# SDRAM_16Mx32.net
KiCad netlist of a schematic drawn in Altium Designer
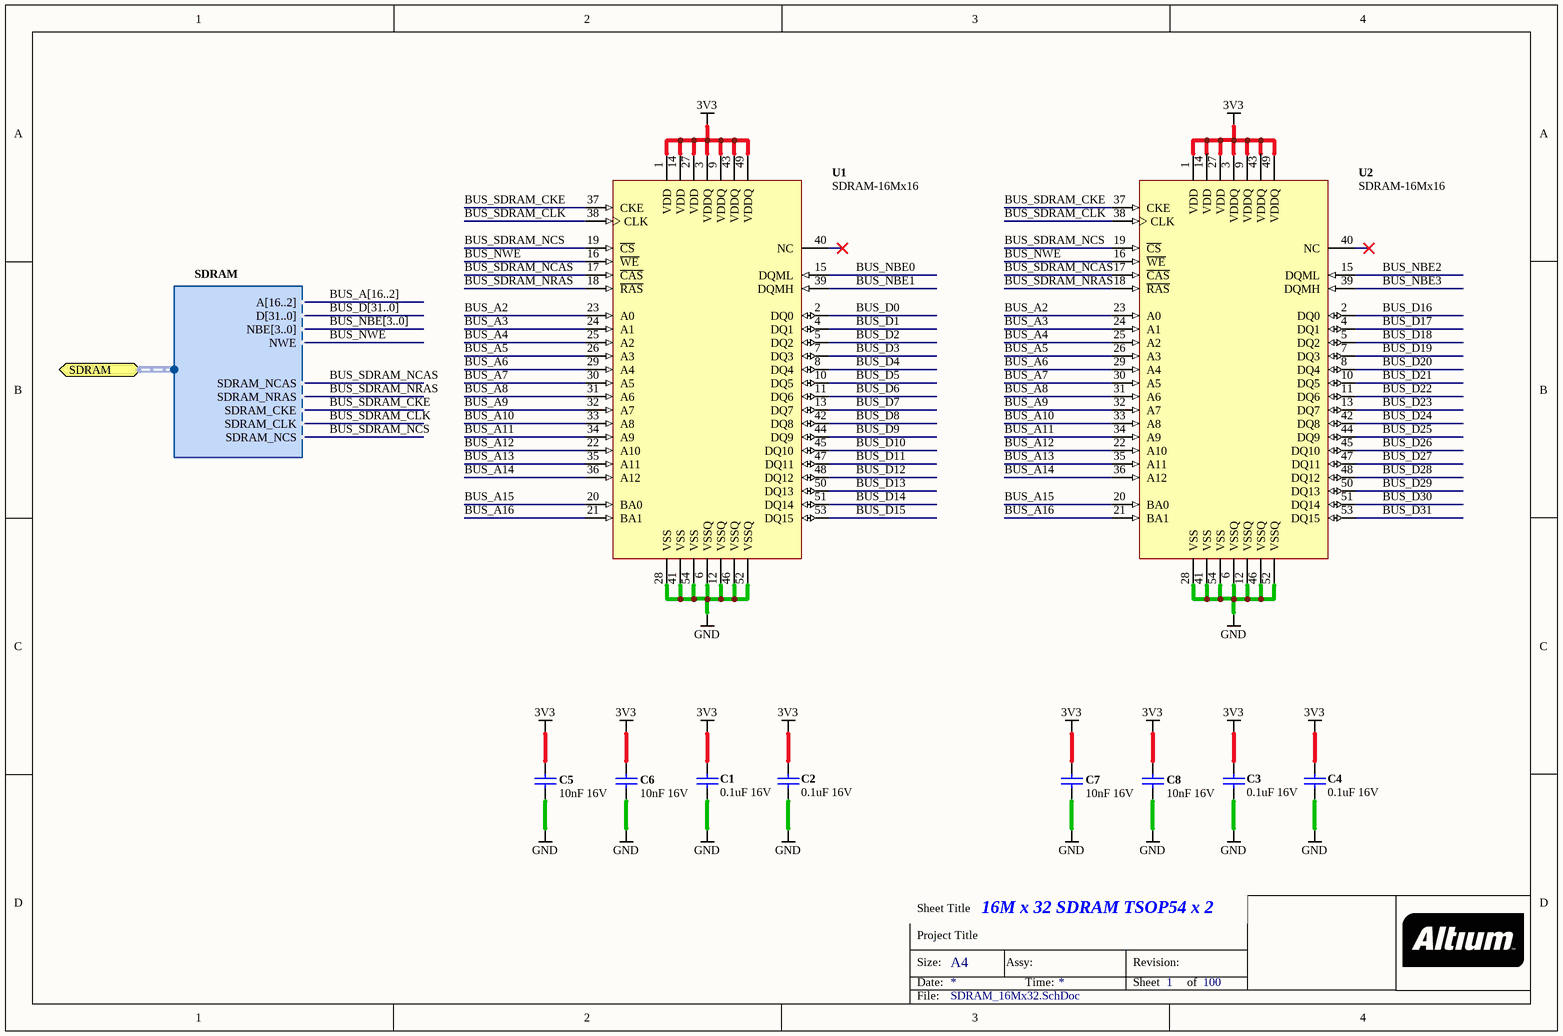
[diagram p0: SDRAM_16Mx32.SchDoc]

(export (version "E")
  (design (tool "Eeschema 10.0.6"))
  (components
    (comp (ref "C1")
      (value "0.1uF 16V")
      (footprint "CAPC1005-STAR")
      (description "Capacitor, Ceramic, 0.1uF 10% 16V 0402 (1005) X7R")
      (fields (field (name "TOLERANCE") "10 %"))
      (libsource (lib "altium-import") (part "root_0_mirrored_CAP-NP_"))
    )
    (comp (ref "C2")
      (value "0.1uF 16V")
      (footprint "CAPC1005-STAR")
      (description "Capacitor, Ceramic, 0.1uF 10% 16V 0402 (1005) X7R")
      (fields (field (name "TOLERANCE") "10 %"))
      (libsource (lib "altium-import") (part "root_0_mirrored_CAP-NP_"))
    )
    (comp (ref "C3")
      (value "0.1uF 16V")
      (footprint "CAPC1005-STAR")
      (description "Capacitor, Ceramic, 0.1uF 10% 16V 0402 (1005) X7R")
      (fields (field (name "TOLERANCE") "10 %"))
      (libsource (lib "altium-import") (part "root_0_mirrored_CAP-NP_"))
    )
    (comp (ref "C4")
      (value "0.1uF 16V")
      (footprint "CAPC1005-STAR")
      (description "Capacitor, Ceramic, 0.1uF 10% 16V 0402 (1005) X7R")
      (fields (field (name "TOLERANCE") "10 %"))
      (libsource (lib "altium-import") (part "root_0_mirrored_CAP-NP_"))
    )
    (comp (ref "C5")
      (value "10nF 16V")
      (footprint "CAPC1005-STAR")
      (description "Capacitor, Ceramic, 10nF 10% 16V 0402 (1005) X7R")
      (fields (field (name "TOLERANCE") "10 %"))
      (libsource (lib "altium-import") (part "root_0_CAP-NP_"))
    )
    (comp (ref "C6")
      (value "10nF 16V")
      (footprint "CAPC1005-STAR")
      (description "Capacitor, Ceramic, 10nF 10% 16V 0402 (1005) X7R")
      (fields (field (name "TOLERANCE") "10 %"))
      (libsource (lib "altium-import") (part "root_0_CAP-NP_"))
    )
    (comp (ref "C7")
      (value "10nF 16V")
      (footprint "CAPC1005-STAR")
      (description "Capacitor, Ceramic, 10nF 10% 16V 0402 (1005) X7R")
      (fields (field (name "TOLERANCE") "10 %"))
      (libsource (lib "altium-import") (part "root_0_CAP-NP_"))
    )
    (comp (ref "C8")
      (value "10nF 16V")
      (footprint "CAPC1005-STAR")
      (description "Capacitor, Ceramic, 10nF 10% 16V 0402 (1005) X7R")
      (fields (field (name "TOLERANCE") "10 %"))
      (libsource (lib "altium-import") (part "root_0_CAP-NP_"))
    )
    (comp (ref "U1")
      (value "SDRAM-16Mx16")
      (footprint "TSOP80P1176-54")
      (description "MT48LC16M16A2TG, 256 Mbit High-Speed CMOS SDRAM, 16Mb x 16Bit x 4 Banks, TSOP54")
      (libsource (lib "altium-import") (part "root_0_MT48LC16M16A2TG_"))
    )
    (comp (ref "U2")
      (value "SDRAM-16Mx16")
      (footprint "TSOP80P1176-54")
      (description "MT48LC16M16A2TG, 256 Mbit High-Speed CMOS SDRAM, 16Mb x 16Bit x 4 Banks, TSOP54")
      (libsource (lib "altium-import") (part "root_0_MT48LC16M16A2TG_"))
    )
  )
  (nets
    (net (code "2") (name "/BUS_A2") (class "Default")
      (node (ref "U1") (pin "23") (pinfunction "A0_23") (pintype "input"))
      (node (ref "U2") (pin "23") (pinfunction "A0_23") (pintype "input"))
    )
    (net (code "3") (name "/BUS_A3") (class "Default")
      (node (ref "U1") (pin "24") (pinfunction "A1_24") (pintype "input"))
      (node (ref "U2") (pin "24") (pinfunction "A1_24") (pintype "input"))
    )
    (net (code "4") (name "/BUS_A4") (class "Default")
      (node (ref "U1") (pin "25") (pinfunction "A2_25") (pintype "input"))
      (node (ref "U2") (pin "25") (pinfunction "A2_25") (pintype "input"))
    )
    (net (code "5") (name "/BUS_A5") (class "Default")
      (node (ref "U1") (pin "26") (pinfunction "A3_26") (pintype "input"))
      (node (ref "U2") (pin "26") (pinfunction "A3_26") (pintype "input"))
    )
    (net (code "6") (name "/BUS_A6") (class "Default")
      (node (ref "U1") (pin "29") (pinfunction "A4_29") (pintype "input"))
      (node (ref "U2") (pin "29") (pinfunction "A4_29") (pintype "input"))
    )
    (net (code "7") (name "/BUS_A7") (class "Default")
      (node (ref "U1") (pin "30") (pinfunction "A5_30") (pintype "input"))
      (node (ref "U2") (pin "30") (pinfunction "A5_30") (pintype "input"))
    )
    (net (code "8") (name "/BUS_A8") (class "Default")
      (node (ref "U1") (pin "31") (pinfunction "A6_31") (pintype "input"))
      (node (ref "U2") (pin "31") (pinfunction "A6_31") (pintype "input"))
    )
    (net (code "9") (name "/BUS_A9") (class "Default")
      (node (ref "U1") (pin "32") (pinfunction "A7_32") (pintype "input"))
      (node (ref "U2") (pin "32") (pinfunction "A7_32") (pintype "input"))
    )
    (net (code "10") (name "/BUS_A10") (class "Default")
      (node (ref "U1") (pin "33") (pinfunction "A8_33") (pintype "input"))
      (node (ref "U2") (pin "33") (pinfunction "A8_33") (pintype "input"))
    )
    (net (code "11") (name "/BUS_A11") (class "Default")
      (node (ref "U1") (pin "34") (pinfunction "A9_34") (pintype "input"))
      (node (ref "U2") (pin "34") (pinfunction "A9_34") (pintype "input"))
    )
    (net (code "12") (name "/BUS_A12") (class "Default")
      (node (ref "U1") (pin "22") (pinfunction "A10_22") (pintype "input"))
      (node (ref "U2") (pin "22") (pinfunction "A10_22") (pintype "input"))
    )
    (net (code "13") (name "/BUS_A13") (class "Default")
      (node (ref "U1") (pin "35") (pinfunction "A11_35") (pintype "input"))
      (node (ref "U2") (pin "35") (pinfunction "A11_35") (pintype "input"))
    )
    (net (code "14") (name "/BUS_A14") (class "Default")
      (node (ref "U1") (pin "36") (pinfunction "A12_36") (pintype "input"))
      (node (ref "U2") (pin "36") (pinfunction "A12_36") (pintype "input"))
    )
    (net (code "15") (name "/BUS_A15") (class "Default")
      (node (ref "U1") (pin "20") (pinfunction "BA0_20") (pintype "input"))
      (node (ref "U2") (pin "20") (pinfunction "BA0_20") (pintype "input"))
    )
    (net (code "16") (name "/BUS_A16") (class "Default")
      (node (ref "U1") (pin "21") (pinfunction "BA1_21") (pintype "input"))
      (node (ref "U2") (pin "21") (pinfunction "BA1_21") (pintype "input"))
    )
    (net (code "18") (name "/BUS_D0") (class "Default")
      (node (ref "U1") (pin "2") (pinfunction "DQ0_2") (pintype "bidirectional"))
    )
    (net (code "19") (name "/BUS_D1") (class "Default")
      (node (ref "U1") (pin "4") (pinfunction "DQ1_4") (pintype "bidirectional"))
    )
    (net (code "20") (name "/BUS_D2") (class "Default")
      (node (ref "U1") (pin "5") (pinfunction "DQ2_5") (pintype "bidirectional"))
    )
    (net (code "21") (name "/BUS_D3") (class "Default")
      (node (ref "U1") (pin "7") (pinfunction "DQ3_7") (pintype "bidirectional"))
    )
    (net (code "22") (name "/BUS_D4") (class "Default")
      (node (ref "U1") (pin "8") (pinfunction "DQ4_8") (pintype "bidirectional"))
    )
    (net (code "23") (name "/BUS_D5") (class "Default")
      (node (ref "U1") (pin "10") (pinfunction "DQ5_10") (pintype "bidirectional"))
    )
    (net (code "24") (name "/BUS_D6") (class "Default")
      (node (ref "U1") (pin "11") (pinfunction "DQ6_11") (pintype "bidirectional"))
    )
    (net (code "25") (name "/BUS_D7") (class "Default")
      (node (ref "U1") (pin "13") (pinfunction "DQ7_13") (pintype "bidirectional"))
    )
    (net (code "26") (name "/BUS_D8") (class "Default")
      (node (ref "U1") (pin "42") (pinfunction "DQ8_42") (pintype "bidirectional"))
    )
    (net (code "27") (name "/BUS_D9") (class "Default")
      (node (ref "U1") (pin "44") (pinfunction "DQ9_44") (pintype "bidirectional"))
    )
    (net (code "28") (name "/BUS_D10") (class "Default")
      (node (ref "U1") (pin "45") (pinfunction "DQ10_45") (pintype "bidirectional"))
    )
    (net (code "29") (name "/BUS_D11") (class "Default")
      (node (ref "U1") (pin "47") (pinfunction "DQ11_47") (pintype "bidirectional"))
    )
    (net (code "30") (name "/BUS_D12") (class "Default")
      (node (ref "U1") (pin "48") (pinfunction "DQ12_48") (pintype "bidirectional"))
    )
    (net (code "31") (name "/BUS_D13") (class "Default")
      (node (ref "U1") (pin "50") (pinfunction "DQ13_50") (pintype "bidirectional"))
    )
    (net (code "32") (name "/BUS_D14") (class "Default")
      (node (ref "U1") (pin "51") (pinfunction "DQ14_51") (pintype "bidirectional"))
    )
    (net (code "33") (name "/BUS_D15") (class "Default")
      (node (ref "U1") (pin "53") (pinfunction "DQ15_53") (pintype "bidirectional"))
    )
    (net (code "34") (name "/BUS_D16") (class "Default")
      (node (ref "U2") (pin "2") (pinfunction "DQ0_2") (pintype "bidirectional"))
    )
    (net (code "35") (name "/BUS_D17") (class "Default")
      (node (ref "U2") (pin "4") (pinfunction "DQ1_4") (pintype "bidirectional"))
    )
    (net (code "36") (name "/BUS_D18") (class "Default")
      (node (ref "U2") (pin "5") (pinfunction "DQ2_5") (pintype "bidirectional"))
    )
    (net (code "37") (name "/BUS_D19") (class "Default")
      (node (ref "U2") (pin "7") (pinfunction "DQ3_7") (pintype "bidirectional"))
    )
    (net (code "38") (name "/BUS_D20") (class "Default")
      (node (ref "U2") (pin "8") (pinfunction "DQ4_8") (pintype "bidirectional"))
    )
    (net (code "39") (name "/BUS_D21") (class "Default")
      (node (ref "U2") (pin "10") (pinfunction "DQ5_10") (pintype "bidirectional"))
    )
    (net (code "40") (name "/BUS_D22") (class "Default")
      (node (ref "U2") (pin "11") (pinfunction "DQ6_11") (pintype "bidirectional"))
    )
    (net (code "41") (name "/BUS_D23") (class "Default")
      (node (ref "U2") (pin "13") (pinfunction "DQ7_13") (pintype "bidirectional"))
    )
    (net (code "42") (name "/BUS_D24") (class "Default")
      (node (ref "U2") (pin "42") (pinfunction "DQ8_42") (pintype "bidirectional"))
    )
    (net (code "43") (name "/BUS_D25") (class "Default")
      (node (ref "U2") (pin "44") (pinfunction "DQ9_44") (pintype "bidirectional"))
    )
    (net (code "44") (name "/BUS_D26") (class "Default")
      (node (ref "U2") (pin "45") (pinfunction "DQ10_45") (pintype "bidirectional"))
    )
    (net (code "45") (name "/BUS_D27") (class "Default")
      (node (ref "U2") (pin "47") (pinfunction "DQ11_47") (pintype "bidirectional"))
    )
    (net (code "46") (name "/BUS_D28") (class "Default")
      (node (ref "U2") (pin "48") (pinfunction "DQ12_48") (pintype "bidirectional"))
    )
    (net (code "47") (name "/BUS_D29") (class "Default")
      (node (ref "U2") (pin "50") (pinfunction "DQ13_50") (pintype "bidirectional"))
    )
    (net (code "48") (name "/BUS_D30") (class "Default")
      (node (ref "U2") (pin "51") (pinfunction "DQ14_51") (pintype "bidirectional"))
    )
    (net (code "49") (name "/BUS_D31") (class "Default")
      (node (ref "U2") (pin "53") (pinfunction "DQ15_53") (pintype "bidirectional"))
    )
    (net (code "51") (name "/BUS_NBE0") (class "Default")
      (node (ref "U1") (pin "15") (pinfunction "DQML_15") (pintype "input"))
    )
    (net (code "52") (name "/BUS_NBE1") (class "Default")
      (node (ref "U1") (pin "39") (pinfunction "DQMH_39") (pintype "input"))
    )
    (net (code "53") (name "/BUS_NBE2") (class "Default")
      (node (ref "U2") (pin "15") (pinfunction "DQML_15") (pintype "input"))
    )
    (net (code "54") (name "/BUS_NBE3") (class "Default")
      (node (ref "U2") (pin "39") (pinfunction "DQMH_39") (pintype "input"))
    )
    (net (code "56") (name "/BUS_NWE") (class "Default")
      (node (ref "U1") (pin "16") (pinfunction "~{WE}_16") (pintype "input"))
      (node (ref "U2") (pin "16") (pinfunction "~{WE}_16") (pintype "input"))
    )
    (net (code "57") (name "/BUS_SDRAM_CKE") (class "Default")
      (node (ref "U1") (pin "37") (pinfunction "CKE_37") (pintype "input"))
      (node (ref "U2") (pin "37") (pinfunction "CKE_37") (pintype "input"))
    )
    (net (code "58") (name "/BUS_SDRAM_CLK") (class "Default")
      (node (ref "U1") (pin "38") (pinfunction "CLK_38") (pintype "input"))
      (node (ref "U2") (pin "38") (pinfunction "CLK_38") (pintype "input"))
    )
    (net (code "59") (name "/BUS_SDRAM_NCAS") (class "Default")
      (node (ref "U1") (pin "17") (pinfunction "~{CAS}_17") (pintype "input"))
      (node (ref "U2") (pin "17") (pinfunction "~{CAS}_17") (pintype "input"))
    )
    (net (code "60") (name "/BUS_SDRAM_NCS") (class "Default")
      (node (ref "U1") (pin "19") (pinfunction "~{CS}_19") (pintype "input"))
      (node (ref "U2") (pin "19") (pinfunction "~{CS}_19") (pintype "input"))
    )
    (net (code "61") (name "/BUS_SDRAM_NRAS") (class "Default")
      (node (ref "U1") (pin "18") (pinfunction "~{RAS}_18") (pintype "input"))
      (node (ref "U2") (pin "18") (pinfunction "~{RAS}_18") (pintype "input"))
    )
    (net (code "63") (name "3V3") (class "Default")
      (node (ref "C1") (pin "1") (pinfunction "1_1") (pintype "passive"))
      (node (ref "C2") (pin "1") (pinfunction "1_1") (pintype "passive"))
      (node (ref "C3") (pin "1") (pinfunction "1_1") (pintype "passive"))
      (node (ref "C4") (pin "1") (pinfunction "1_1") (pintype "passive"))
      (node (ref "C5") (pin "1") (pinfunction "1_1") (pintype "passive"))
      (node (ref "C6") (pin "1") (pinfunction "1_1") (pintype "passive"))
      (node (ref "C7") (pin "1") (pinfunction "1_1") (pintype "passive"))
      (node (ref "C8") (pin "1") (pinfunction "1_1") (pintype "passive"))
      (node (ref "U1") (pin "1") (pinfunction "VDD_1") (pintype "power_in"))
      (node (ref "U1") (pin "14") (pinfunction "VDD_14") (pintype "power_in"))
      (node (ref "U1") (pin "27") (pinfunction "VDD_27") (pintype "power_in"))
      (node (ref "U1") (pin "3") (pinfunction "VDDQ_3") (pintype "power_in"))
      (node (ref "U1") (pin "43") (pinfunction "VDDQ_43") (pintype "power_in"))
      (node (ref "U1") (pin "49") (pinfunction "VDDQ_49") (pintype "power_in"))
      (node (ref "U1") (pin "9") (pinfunction "VDDQ_9") (pintype "power_in"))
      (node (ref "U2") (pin "1") (pinfunction "VDD_1") (pintype "power_in"))
      (node (ref "U2") (pin "14") (pinfunction "VDD_14") (pintype "power_in"))
      (node (ref "U2") (pin "27") (pinfunction "VDD_27") (pintype "power_in"))
      (node (ref "U2") (pin "3") (pinfunction "VDDQ_3") (pintype "power_in"))
      (node (ref "U2") (pin "43") (pinfunction "VDDQ_43") (pintype "power_in"))
      (node (ref "U2") (pin "49") (pinfunction "VDDQ_49") (pintype "power_in"))
      (node (ref "U2") (pin "9") (pinfunction "VDDQ_9") (pintype "power_in"))
    )
    (net (code "64") (name "GND") (class "Default")
      (node (ref "C1") (pin "2") (pinfunction "2_2") (pintype "passive"))
      (node (ref "C2") (pin "2") (pinfunction "2_2") (pintype "passive"))
      (node (ref "C3") (pin "2") (pinfunction "2_2") (pintype "passive"))
      (node (ref "C4") (pin "2") (pinfunction "2_2") (pintype "passive"))
      (node (ref "C5") (pin "2") (pinfunction "2_2") (pintype "passive"))
      (node (ref "C6") (pin "2") (pinfunction "2_2") (pintype "passive"))
      (node (ref "C7") (pin "2") (pinfunction "2_2") (pintype "passive"))
      (node (ref "C8") (pin "2") (pinfunction "2_2") (pintype "passive"))
      (node (ref "U1") (pin "12") (pinfunction "VSSQ_12") (pintype "power_in"))
      (node (ref "U1") (pin "28") (pinfunction "VSS_28") (pintype "power_in"))
      (node (ref "U1") (pin "41") (pinfunction "VSS_41") (pintype "power_in"))
      (node (ref "U1") (pin "46") (pinfunction "VSSQ_46") (pintype "power_in"))
      (node (ref "U1") (pin "52") (pinfunction "VSSQ_52") (pintype "power_in"))
      (node (ref "U1") (pin "54") (pinfunction "VSS_54") (pintype "power_in"))
      (node (ref "U1") (pin "6") (pinfunction "VSSQ_6") (pintype "power_in"))
      (node (ref "U2") (pin "12") (pinfunction "VSSQ_12") (pintype "power_in"))
      (node (ref "U2") (pin "28") (pinfunction "VSS_28") (pintype "power_in"))
      (node (ref "U2") (pin "41") (pinfunction "VSS_41") (pintype "power_in"))
      (node (ref "U2") (pin "46") (pinfunction "VSSQ_46") (pintype "power_in"))
      (node (ref "U2") (pin "52") (pinfunction "VSSQ_52") (pintype "power_in"))
      (node (ref "U2") (pin "54") (pinfunction "VSS_54") (pintype "power_in"))
      (node (ref "U2") (pin "6") (pinfunction "VSSQ_6") (pintype "power_in"))
    )
    (net (code "65") (name "unconnected-(U1-NC-Pad40)") (class "Default")
      (node (ref "U1") (pin "40") (pinfunction "NC_40") (pintype "passive+no_connect"))
    )
    (net (code "66") (name "unconnected-(U2-NC-Pad40)") (class "Default")
      (node (ref "U2") (pin "40") (pinfunction "NC_40") (pintype "passive+no_connect"))
    )
  )
)
